# Plugs.net
KiCad netlist of a schematic drawn in Altium Designer
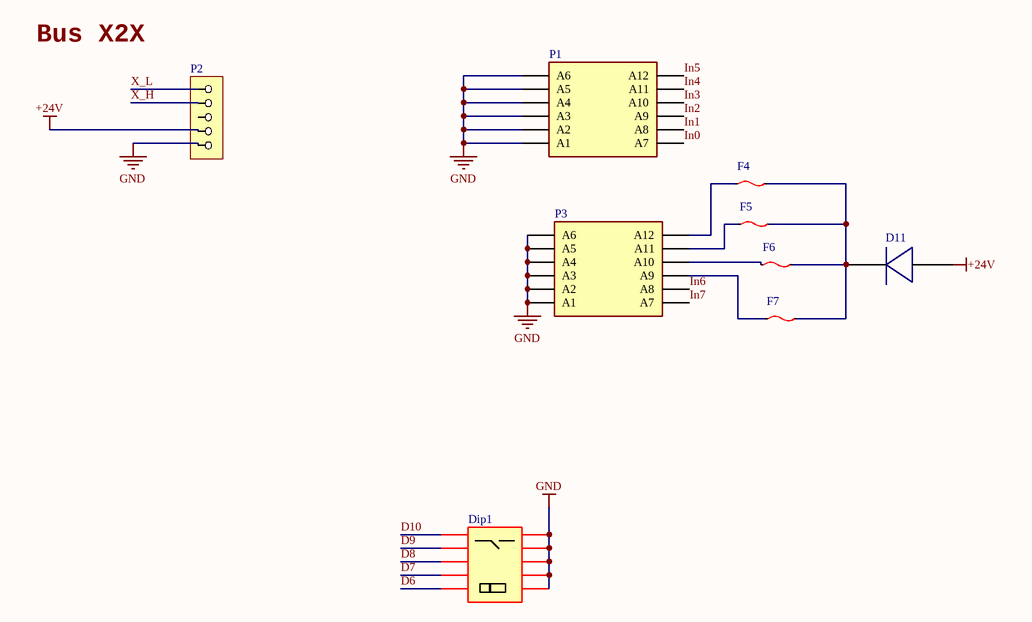
[diagram p0: Plugs.SchDoc]

(export (version "E")
  (design (tool "Eeschema 10.0.6"))
  (components
    (comp (ref "D11")
      (value "~")
      (footprint "B340A-13-F")
      (fields (field (name "PART NUMBER") "B360A-13-F"))
      (libsource (lib "kontr") (part "B340A-13-F"))
    )
    (comp (ref "Dip1")
      (value "~")
      (footprint "DipSwitch 5")
      (fields (field (name "PART NUMBER") "DS1040-05RT"))
      (libsource (lib "kontr") (part "DipSwitch5"))
    )
    (comp (ref "F4")
      (value "~")
      (footprint "MSMF")
      (fields (field (name "PART NUMBER") "MF-MSMF010-2"))
      (libsource (lib "kontr") (part "MSMF"))
    )
    (comp (ref "F5")
      (value "~")
      (footprint "MSMF")
      (fields (field (name "PART NUMBER") "MF-MSMF010-2"))
      (libsource (lib "kontr") (part "MSMF"))
    )
    (comp (ref "F6")
      (value "~")
      (footprint "MSMF")
      (fields (field (name "PART NUMBER") "MF-MSMF010-2"))
      (libsource (lib "kontr") (part "MSMF"))
    )
    (comp (ref "F7")
      (value "~")
      (footprint "MSMF")
      (fields (field (name "PART NUMBER") "MF-MSMF010-2"))
      (libsource (lib "kontr") (part "MSMF"))
    )
    (comp (ref "P1")
      (value "~")
      (footprint "PCB DI:mcd 1,5/6-G1-3.81")
      (fields (field (name "PART NUMBER") "MCD 1.5/6 Phoenix") (field (name "PUBLISHER") "Altium Limited"))
      (libsource (lib "kontr") (part "MCD 1.5/6 Phoenix"))
    )
    (comp (ref "P2")
      (value "~")
      (footprint "PhClass5")
      (fields (field (name "PART NUMBER") "MSTBA 2,5/ 5-G-5,08 - 1757271"))
      (libsource (lib "kontr") (part "EMSTBA 2.5/5-G-5.08"))
    )
    (comp (ref "P3")
      (value "~")
      (footprint "PCB DI:mcd 1,5/6-G1-3.81")
      (fields (field (name "PART NUMBER") "MCD 1.5/6 Phoenix") (field (name "PUBLISHER") "Altium Limited"))
      (libsource (lib "kontr") (part "MCD 1.5/6 Phoenix"))
    )
  )
  (nets
    (net (code "1") (name "+24V") (class "Default")
      (node (ref "D11") (pin "2") (pinfunction "1_2") (pintype "passive"))
      (node (ref "P2") (pin "4") (pinfunction "2_4") (pintype "passive"))
    )
    (net (code "2") (name "/D6") (class "Default")
      (node (ref "Dip1") (pin "16") (pinfunction "2_16") (pintype "passive"))
    )
    (net (code "3") (name "/D7") (class "Default")
      (node (ref "Dip1") (pin "15") (pinfunction "4_15") (pintype "passive"))
    )
    (net (code "4") (name "/D8") (class "Default")
      (node (ref "Dip1") (pin "14") (pinfunction "6_14") (pintype "passive"))
    )
    (net (code "5") (name "/D9") (class "Default")
      (node (ref "Dip1") (pin "13") (pinfunction "8_13") (pintype "passive"))
    )
    (net (code "6") (name "/D10") (class "Default")
      (node (ref "Dip1") (pin "12") (pinfunction "10_12") (pintype "passive"))
    )
    (net (code "7") (name "/In0") (class "Default")
      (node (ref "P1") (pin "12") (pinfunction "A7_12") (pintype "passive"))
    )
    (net (code "8") (name "/In1") (class "Default")
      (node (ref "P1") (pin "10") (pinfunction "A8_10") (pintype "passive"))
    )
    (net (code "9") (name "/In2") (class "Default")
      (node (ref "P1") (pin "8") (pinfunction "A9_8") (pintype "passive"))
    )
    (net (code "10") (name "/In3") (class "Default")
      (node (ref "P1") (pin "6") (pinfunction "A10_6") (pintype "passive"))
    )
    (net (code "11") (name "/In4") (class "Default")
      (node (ref "P1") (pin "4") (pinfunction "A11_4") (pintype "passive"))
    )
    (net (code "12") (name "/In5") (class "Default")
      (node (ref "P1") (pin "2") (pinfunction "A12_2") (pintype "passive"))
    )
    (net (code "13") (name "/In6") (class "Default")
      (node (ref "P3") (pin "10") (pinfunction "A8_10") (pintype "passive"))
    )
    (net (code "14") (name "/In7") (class "Default")
      (node (ref "P3") (pin "12") (pinfunction "A7_12") (pintype "passive"))
    )
    (net (code "15") (name "/X_H") (class "Default")
      (node (ref "P2") (pin "2") (pinfunction "2_2") (pintype "passive"))
    )
    (net (code "16") (name "/X_L") (class "Default")
      (node (ref "P2") (pin "1") (pinfunction "1_1") (pintype "passive"))
    )
    (net (code "17") (name "GND") (class "Default")
      (node (ref "Dip1") (pin "1") (pinfunction "1_1") (pintype "passive"))
      (node (ref "Dip1") (pin "2") (pinfunction "3_2") (pintype "passive"))
      (node (ref "Dip1") (pin "3") (pinfunction "5_3") (pintype "passive"))
      (node (ref "Dip1") (pin "4") (pinfunction "7_4") (pintype "passive"))
      (node (ref "Dip1") (pin "5") (pinfunction "9_5") (pintype "passive"))
      (node (ref "P1") (pin "1") (pinfunction "A6_1") (pintype "passive"))
      (node (ref "P1") (pin "11") (pinfunction "A1_11") (pintype "passive"))
      (node (ref "P1") (pin "3") (pinfunction "A5_3") (pintype "passive"))
      (node (ref "P1") (pin "5") (pinfunction "A4_5") (pintype "passive"))
      (node (ref "P1") (pin "7") (pinfunction "A3_7") (pintype "passive"))
      (node (ref "P1") (pin "9") (pinfunction "A2_9") (pintype "passive"))
      (node (ref "P2") (pin "5") (pinfunction "3_5") (pintype "passive"))
      (node (ref "P3") (pin "1") (pinfunction "A6_1") (pintype "passive"))
      (node (ref "P3") (pin "11") (pinfunction "A1_11") (pintype "passive"))
      (node (ref "P3") (pin "3") (pinfunction "A5_3") (pintype "passive"))
      (node (ref "P3") (pin "5") (pinfunction "A4_5") (pintype "passive"))
      (node (ref "P3") (pin "7") (pinfunction "A3_7") (pintype "passive"))
      (node (ref "P3") (pin "9") (pinfunction "A2_9") (pintype "passive"))
    )
    (net (code "18") (name "Net-(D11-Pad1)") (class "Default")
      (node (ref "D11") (pin "1") (pinfunction "1_1") (pintype "passive"))
      (node (ref "F4") (pin "1") (pinfunction "1_1") (pintype "passive"))
      (node (ref "F5") (pin "1") (pinfunction "1_1") (pintype "passive"))
      (node (ref "F6") (pin "1") (pinfunction "1_1") (pintype "passive"))
      (node (ref "F7") (pin "1") (pinfunction "1_1") (pintype "passive"))
    )
    (net (code "19") (name "Net-(P3-A9)") (class "Default")
      (node (ref "F7") (pin "0") (pinfunction "0_0") (pintype "passive"))
      (node (ref "P3") (pin "8") (pinfunction "A9_8") (pintype "passive"))
    )
    (net (code "20") (name "Net-(P3-A10)") (class "Default")
      (node (ref "F6") (pin "0") (pinfunction "0_0") (pintype "passive"))
      (node (ref "P3") (pin "6") (pinfunction "A10_6") (pintype "passive"))
    )
    (net (code "21") (name "Net-(P3-A11)") (class "Default")
      (node (ref "F5") (pin "0") (pinfunction "0_0") (pintype "passive"))
      (node (ref "P3") (pin "4") (pinfunction "A11_4") (pintype "passive"))
    )
    (net (code "22") (name "Net-(P3-A12)") (class "Default")
      (node (ref "F4") (pin "0") (pinfunction "0_0") (pintype "passive"))
      (node (ref "P3") (pin "2") (pinfunction "A12_2") (pintype "passive"))
    )
    (net (code "23") (name "unconnected-(P2-Pad3)") (class "Default")
      (node (ref "P2") (pin "3") (pinfunction "3_3") (pintype "passive"))
    )
  )
)
